# ESP_nixie_clock.net
KiCad netlist of a schematic drawn in EAGLE
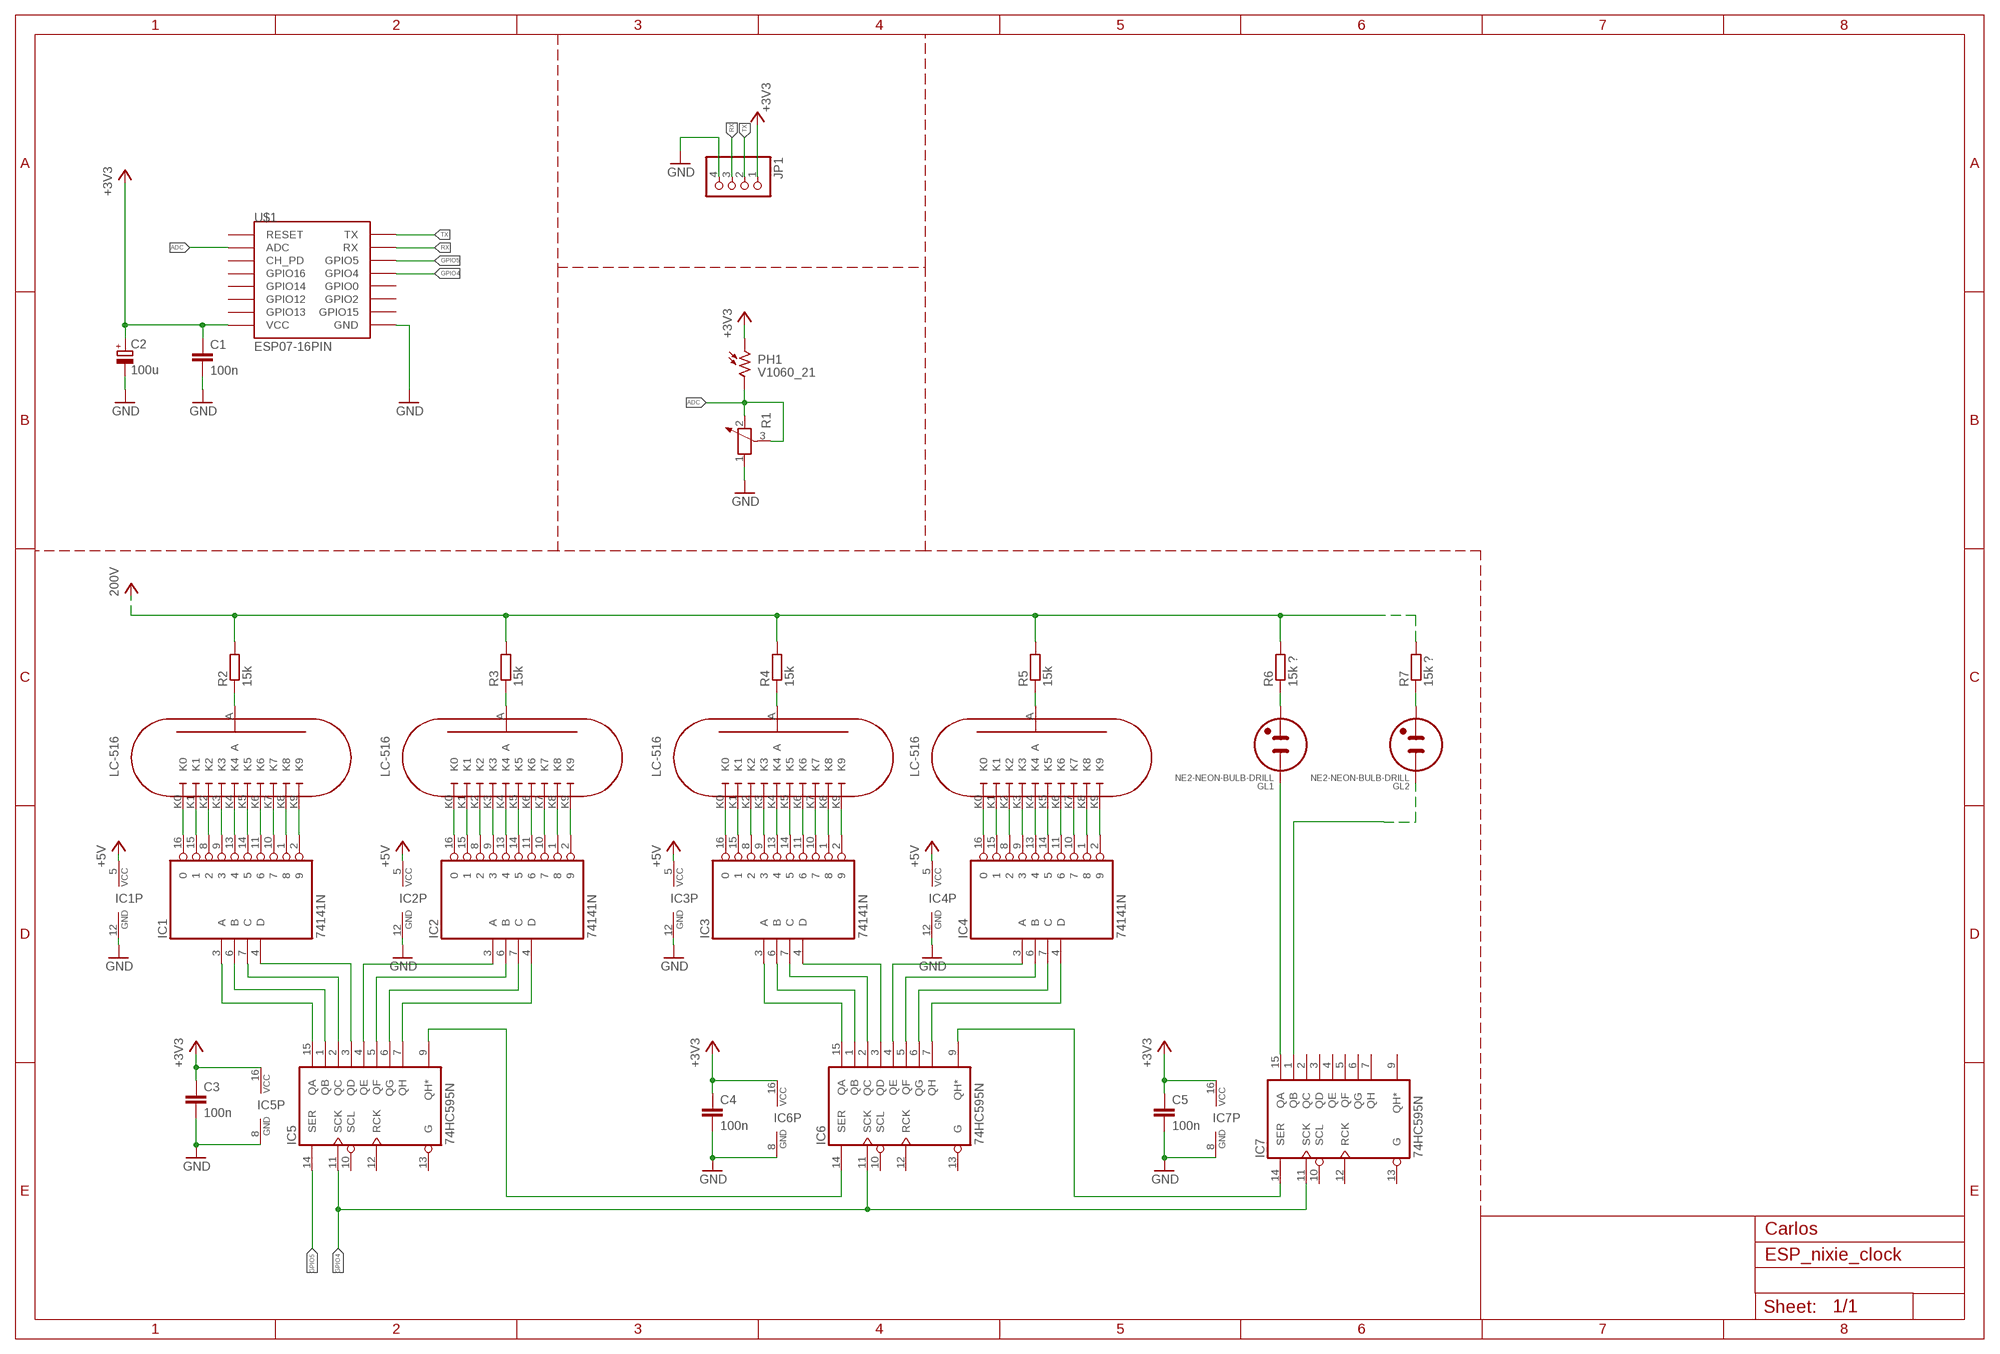
[diagram p0: schematic, sheet 1]

(export (version "E")
  (design (tool "Eeschema 10.0.6"))
  (components
    (comp (ref "C1")
      (value "100n")
      (footprint "eagle-import:C0805K")
      (libsource (lib "eagle-import") (part "C-EUC0805K"))
    )
    (comp (ref "C2")
      (value "100u")
      (footprint "eagle-import:153CLV-0810")
      (libsource (lib "eagle-import") (part "CPOL-EU153CLV-0810"))
    )
    (comp (ref "C3")
      (value "100n")
      (footprint "eagle-import:C0805K")
      (libsource (lib "eagle-import") (part "C-EUC0805K"))
    )
    (comp (ref "C4")
      (value "100n")
      (footprint "eagle-import:C0805K")
      (libsource (lib "eagle-import") (part "C-EUC0805K"))
    )
    (comp (ref "C5")
      (value "100n")
      (footprint "eagle-import:C0805K")
      (libsource (lib "eagle-import") (part "C-EUC0805K"))
    )
    (comp (ref "GL1")
      (value "NE2-NEON-BULB-DRILL")
      (footprint "eagle-import:NE2-NEON-BULB-DRILL")
      (libsource (lib "eagle-import") (part "NE2-NEON-BULB-DRILL"))
    )
    (comp (ref "GL2")
      (value "NE2-NEON-BULB-DRILL")
      (footprint "eagle-import:NE2-NEON-BULB-DRILL")
      (libsource (lib "eagle-import") (part "NE2-NEON-BULB-DRILL"))
    )
    (comp (ref "IC1")
      (value "74141N")
      (footprint "eagle-import:DIL16")
      (libsource (lib "eagle-import") (part "74141N"))
    )
    (comp (ref "IC2")
      (value "74141N")
      (footprint "eagle-import:DIL16")
      (libsource (lib "eagle-import") (part "74141N"))
    )
    (comp (ref "IC3")
      (value "74141N")
      (footprint "eagle-import:DIL16")
      (libsource (lib "eagle-import") (part "74141N"))
    )
    (comp (ref "IC4")
      (value "74141N")
      (footprint "eagle-import:DIL16")
      (libsource (lib "eagle-import") (part "74141N"))
    )
    (comp (ref "IC5")
      (value "74HC595N")
      (footprint "eagle-import:DIL16")
      (libsource (lib "eagle-import") (part "74595NHC"))
    )
    (comp (ref "IC6")
      (value "74HC595N")
      (footprint "eagle-import:DIL16")
      (libsource (lib "eagle-import") (part "74595NHC"))
    )
    (comp (ref "IC7")
      (value "74HC595N")
      (footprint "eagle-import:DIL16")
      (libsource (lib "eagle-import") (part "74595NHC"))
    )
    (comp (ref "JP1")
      (value "PINHD-1X4/90")
      (footprint "eagle-import:1X04_90")
      (libsource (lib "eagle-import") (part "PINHD-1X4/90"))
    )
    (comp (ref "PH1")
      (value "V1060_21")
      (footprint "eagle-import:TO-5_V10")
      (libsource (lib "eagle-import") (part "?1060V_21"))
    )
    (comp (ref "R1")
      (value "POTENTIOMETER_PT-10")
      (footprint "eagle-import:PT-10")
      (libsource (lib "eagle-import") (part "POTENTIOMETER_PT-10"))
    )
    (comp (ref "R2")
      (value "15k")
      (footprint "eagle-import:0207_10")
      (libsource (lib "eagle-import") (part "R-EU_0207/10"))
    )
    (comp (ref "R3")
      (value "15k")
      (footprint "eagle-import:0207_10")
      (libsource (lib "eagle-import") (part "R-EU_0207/10"))
    )
    (comp (ref "R4")
      (value "15k")
      (footprint "eagle-import:0207_10")
      (libsource (lib "eagle-import") (part "R-EU_0207/10"))
    )
    (comp (ref "R5")
      (value "15k")
      (footprint "eagle-import:0207_10")
      (libsource (lib "eagle-import") (part "R-EU_0207/10"))
    )
    (comp (ref "R6")
      (value "15k ?")
      (footprint "eagle-import:0207_10")
      (libsource (lib "eagle-import") (part "R-EU_0207/10"))
    )
    (comp (ref "R7")
      (value "15k ?")
      (footprint "eagle-import:0207_10")
      (libsource (lib "eagle-import") (part "R-EU_0207/10"))
    )
    (comp (ref "U$1")
      (value "ESP07-16PIN")
      (footprint "eagle-import:ESP07-16PIN")
      (libsource (lib "eagle-import") (part "ESP07-16PIN"))
    )
    (comp (ref "U$2")
      (value "LC-516")
      (footprint "eagle-import:LC-516")
      (libsource (lib "eagle-import") (part "LC-516"))
    )
    (comp (ref "U$3")
      (value "LC-516")
      (footprint "eagle-import:LC-516")
      (libsource (lib "eagle-import") (part "LC-516"))
    )
    (comp (ref "U$4")
      (value "LC-516")
      (footprint "eagle-import:LC-516")
      (libsource (lib "eagle-import") (part "LC-516"))
    )
    (comp (ref "U$5")
      (value "LC-516")
      (footprint "eagle-import:LC-516")
      (libsource (lib "eagle-import") (part "LC-516"))
    )
  )
  (nets
    (net (code "1") (name "+3V3") (class "Default")
      (node (ref "C1") (pin "1") (pinfunction "1_1") (pintype "passive"))
      (node (ref "C2") (pin "+") (pinfunction "+_+") (pintype "passive"))
      (node (ref "C3") (pin "1") (pinfunction "1_1") (pintype "passive"))
      (node (ref "C4") (pin "1") (pinfunction "1_1") (pintype "passive"))
      (node (ref "C5") (pin "1") (pinfunction "1_1") (pintype "passive"))
      (node (ref "IC5") (pin "16") (pinfunction "VCC_16") (pintype "power_in"))
      (node (ref "IC6") (pin "16") (pinfunction "VCC_16") (pintype "power_in"))
      (node (ref "IC7") (pin "16") (pinfunction "VCC_16") (pintype "power_in"))
      (node (ref "JP1") (pin "1") (pinfunction "1_1") (pintype "passive"))
      (node (ref "PH1") (pin "1") (pinfunction "1_1") (pintype "passive"))
      (node (ref "U$1") (pin "VCC") (pinfunction "VCC_VCC") (pintype "bidirectional"))
    )
    (net (code "2") (name "+5V") (class "Default")
      (node (ref "IC1") (pin "5") (pinfunction "VCC_5") (pintype "power_in"))
      (node (ref "IC2") (pin "5") (pinfunction "VCC_5") (pintype "power_in"))
      (node (ref "IC3") (pin "5") (pinfunction "VCC_5") (pintype "power_in"))
      (node (ref "IC4") (pin "5") (pinfunction "VCC_5") (pintype "power_in"))
    )
    (net (code "3") (name "200V") (class "Default")
      (node (ref "R2") (pin "2") (pinfunction "2_2") (pintype "passive"))
      (node (ref "R3") (pin "2") (pinfunction "2_2") (pintype "passive"))
      (node (ref "R4") (pin "2") (pinfunction "2_2") (pintype "passive"))
      (node (ref "R5") (pin "2") (pinfunction "2_2") (pintype "passive"))
      (node (ref "R6") (pin "2") (pinfunction "2_2") (pintype "passive"))
      (node (ref "R7") (pin "2") (pinfunction "2_2") (pintype "passive"))
    )
    (net (code "4") (name "ADC") (class "Default")
      (node (ref "PH1") (pin "2") (pinfunction "2_2") (pintype "passive"))
      (node (ref "R1") (pin "2") (pinfunction "2_2") (pintype "passive"))
      (node (ref "R1") (pin "3") (pinfunction "3_3") (pintype "passive"))
      (node (ref "U$1") (pin "ADC") (pinfunction "ADC_ADC") (pintype "bidirectional"))
    )
    (net (code "5") (name "GND") (class "Default")
      (node (ref "C1") (pin "2") (pinfunction "2_2") (pintype "passive"))
      (node (ref "C2") (pin "-") (pinfunction "-_-") (pintype "passive"))
      (node (ref "C3") (pin "2") (pinfunction "2_2") (pintype "passive"))
      (node (ref "C4") (pin "2") (pinfunction "2_2") (pintype "passive"))
      (node (ref "C5") (pin "2") (pinfunction "2_2") (pintype "passive"))
      (node (ref "IC1") (pin "12") (pinfunction "GND_12") (pintype "power_in"))
      (node (ref "IC2") (pin "12") (pinfunction "GND_12") (pintype "power_in"))
      (node (ref "IC3") (pin "12") (pinfunction "GND_12") (pintype "power_in"))
      (node (ref "IC4") (pin "12") (pinfunction "GND_12") (pintype "power_in"))
      (node (ref "IC5") (pin "8") (pinfunction "GND_8") (pintype "power_in"))
      (node (ref "IC6") (pin "8") (pinfunction "GND_8") (pintype "power_in"))
      (node (ref "IC7") (pin "8") (pinfunction "GND_8") (pintype "power_in"))
      (node (ref "JP1") (pin "4") (pinfunction "4_4") (pintype "passive"))
      (node (ref "R1") (pin "1") (pinfunction "1_1") (pintype "passive"))
      (node (ref "U$1") (pin "GND") (pinfunction "GND_GND") (pintype "bidirectional"))
    )
    (net (code "6") (name "GPIO4") (class "Default")
      (node (ref "IC5") (pin "11") (pinfunction "SCK_11") (pintype "input"))
      (node (ref "IC6") (pin "11") (pinfunction "SCK_11") (pintype "input"))
      (node (ref "IC7") (pin "11") (pinfunction "SCK_11") (pintype "input"))
      (node (ref "U$1") (pin "GPIO5") (pinfunction "GPIO4_GPIO5") (pintype "bidirectional"))
    )
    (net (code "7") (name "GPIO5") (class "Default")
      (node (ref "IC5") (pin "14") (pinfunction "SER_14") (pintype "input"))
      (node (ref "U$1") (pin "GPIO4") (pinfunction "GPIO5_GPIO4") (pintype "bidirectional"))
    )
    (net (code "8") (name "Net-(GL1-A)") (class "Default")
      (node (ref "GL1") (pin "1") (pinfunction "A_1") (pintype "passive"))
      (node (ref "IC7") (pin "15") (pinfunction "QA_15") (pintype "tri_state"))
    )
    (net (code "9") (name "Net-(GL1-A1)") (class "Default")
      (node (ref "GL1") (pin "2") (pinfunction "A1_2") (pintype "passive"))
      (node (ref "R6") (pin "1") (pinfunction "1_1") (pintype "passive"))
    )
    (net (code "10") (name "Net-(GL2-A)") (class "Default")
      (node (ref "GL2") (pin "1") (pinfunction "A_1") (pintype "passive"))
      (node (ref "IC7") (pin "1") (pinfunction "QB_1") (pintype "tri_state"))
    )
    (net (code "11") (name "Net-(GL2-A1)") (class "Default")
      (node (ref "GL2") (pin "2") (pinfunction "A1_2") (pintype "passive"))
      (node (ref "R7") (pin "1") (pinfunction "1_1") (pintype "passive"))
    )
    (net (code "12") (name "Net-(IC1A-0)") (class "Default")
      (node (ref "IC1") (pin "16") (pinfunction "0_16") (pintype "open_collector"))
      (node (ref "U$2") (pin "K0") (pinfunction "K0_K0") (pintype "bidirectional"))
    )
    (net (code "13") (name "Net-(IC1A-1)") (class "Default")
      (node (ref "IC1") (pin "15") (pinfunction "1_15") (pintype "open_collector"))
      (node (ref "U$2") (pin "K1") (pinfunction "K1_K1") (pintype "bidirectional"))
    )
    (net (code "14") (name "Net-(IC1A-2)") (class "Default")
      (node (ref "IC1") (pin "8") (pinfunction "2_8") (pintype "open_collector"))
      (node (ref "U$2") (pin "K2") (pinfunction "K2_K2") (pintype "bidirectional"))
    )
    (net (code "15") (name "Net-(IC1A-3)") (class "Default")
      (node (ref "IC1") (pin "9") (pinfunction "3_9") (pintype "open_collector"))
      (node (ref "U$2") (pin "K3") (pinfunction "K3_K3") (pintype "bidirectional"))
    )
    (net (code "16") (name "Net-(IC1A-4)") (class "Default")
      (node (ref "IC1") (pin "13") (pinfunction "4_13") (pintype "open_collector"))
      (node (ref "U$2") (pin "K4") (pinfunction "K4_K4") (pintype "bidirectional"))
    )
    (net (code "17") (name "Net-(IC1A-5)") (class "Default")
      (node (ref "IC1") (pin "14") (pinfunction "5_14") (pintype "open_collector"))
      (node (ref "U$2") (pin "K5") (pinfunction "K5_K5") (pintype "bidirectional"))
    )
    (net (code "18") (name "Net-(IC1A-6)") (class "Default")
      (node (ref "IC1") (pin "11") (pinfunction "6_11") (pintype "open_collector"))
      (node (ref "U$2") (pin "K6") (pinfunction "K6_K6") (pintype "bidirectional"))
    )
    (net (code "19") (name "Net-(IC1A-7)") (class "Default")
      (node (ref "IC1") (pin "10") (pinfunction "7_10") (pintype "open_collector"))
      (node (ref "U$2") (pin "K7") (pinfunction "K7_K7") (pintype "bidirectional"))
    )
    (net (code "20") (name "Net-(IC1A-8)") (class "Default")
      (node (ref "IC1") (pin "1") (pinfunction "8_1") (pintype "open_collector"))
      (node (ref "U$2") (pin "K8") (pinfunction "K8_K8") (pintype "bidirectional"))
    )
    (net (code "21") (name "Net-(IC1A-9)") (class "Default")
      (node (ref "IC1") (pin "2") (pinfunction "9_2") (pintype "open_collector"))
      (node (ref "U$2") (pin "K9") (pinfunction "K9_K9") (pintype "bidirectional"))
    )
    (net (code "22") (name "Net-(IC1A-A)") (class "Default")
      (node (ref "IC1") (pin "3") (pinfunction "A_3") (pintype "input"))
      (node (ref "IC5") (pin "15") (pinfunction "QA_15") (pintype "tri_state"))
    )
    (net (code "23") (name "Net-(IC1A-B)") (class "Default")
      (node (ref "IC1") (pin "6") (pinfunction "B_6") (pintype "input"))
      (node (ref "IC5") (pin "1") (pinfunction "QB_1") (pintype "tri_state"))
    )
    (net (code "24") (name "Net-(IC1A-C)") (class "Default")
      (node (ref "IC1") (pin "7") (pinfunction "C_7") (pintype "input"))
      (node (ref "IC5") (pin "2") (pinfunction "QC_2") (pintype "tri_state"))
    )
    (net (code "25") (name "Net-(IC1A-D)") (class "Default")
      (node (ref "IC1") (pin "4") (pinfunction "D_4") (pintype "input"))
      (node (ref "IC5") (pin "3") (pinfunction "QD_3") (pintype "tri_state"))
    )
    (net (code "26") (name "Net-(IC2A-0)") (class "Default")
      (node (ref "IC2") (pin "16") (pinfunction "0_16") (pintype "open_collector"))
      (node (ref "U$3") (pin "K0") (pinfunction "K0_K0") (pintype "bidirectional"))
    )
    (net (code "27") (name "Net-(IC2A-1)") (class "Default")
      (node (ref "IC2") (pin "15") (pinfunction "1_15") (pintype "open_collector"))
      (node (ref "U$3") (pin "K1") (pinfunction "K1_K1") (pintype "bidirectional"))
    )
    (net (code "28") (name "Net-(IC2A-2)") (class "Default")
      (node (ref "IC2") (pin "8") (pinfunction "2_8") (pintype "open_collector"))
      (node (ref "U$3") (pin "K2") (pinfunction "K2_K2") (pintype "bidirectional"))
    )
    (net (code "29") (name "Net-(IC2A-3)") (class "Default")
      (node (ref "IC2") (pin "9") (pinfunction "3_9") (pintype "open_collector"))
      (node (ref "U$3") (pin "K3") (pinfunction "K3_K3") (pintype "bidirectional"))
    )
    (net (code "30") (name "Net-(IC2A-4)") (class "Default")
      (node (ref "IC2") (pin "13") (pinfunction "4_13") (pintype "open_collector"))
      (node (ref "U$3") (pin "K4") (pinfunction "K4_K4") (pintype "bidirectional"))
    )
    (net (code "31") (name "Net-(IC2A-5)") (class "Default")
      (node (ref "IC2") (pin "14") (pinfunction "5_14") (pintype "open_collector"))
      (node (ref "U$3") (pin "K5") (pinfunction "K5_K5") (pintype "bidirectional"))
    )
    (net (code "32") (name "Net-(IC2A-6)") (class "Default")
      (node (ref "IC2") (pin "11") (pinfunction "6_11") (pintype "open_collector"))
      (node (ref "U$3") (pin "K6") (pinfunction "K6_K6") (pintype "bidirectional"))
    )
    (net (code "33") (name "Net-(IC2A-7)") (class "Default")
      (node (ref "IC2") (pin "10") (pinfunction "7_10") (pintype "open_collector"))
      (node (ref "U$3") (pin "K7") (pinfunction "K7_K7") (pintype "bidirectional"))
    )
    (net (code "34") (name "Net-(IC2A-8)") (class "Default")
      (node (ref "IC2") (pin "1") (pinfunction "8_1") (pintype "open_collector"))
      (node (ref "U$3") (pin "K8") (pinfunction "K8_K8") (pintype "bidirectional"))
    )
    (net (code "35") (name "Net-(IC2A-9)") (class "Default")
      (node (ref "IC2") (pin "2") (pinfunction "9_2") (pintype "open_collector"))
      (node (ref "U$3") (pin "K9") (pinfunction "K9_K9") (pintype "bidirectional"))
    )
    (net (code "36") (name "Net-(IC2A-A)") (class "Default")
      (node (ref "IC2") (pin "3") (pinfunction "A_3") (pintype "input"))
      (node (ref "IC5") (pin "4") (pinfunction "QE_4") (pintype "tri_state"))
    )
    (net (code "37") (name "Net-(IC2A-B)") (class "Default")
      (node (ref "IC2") (pin "6") (pinfunction "B_6") (pintype "input"))
      (node (ref "IC5") (pin "5") (pinfunction "QF_5") (pintype "tri_state"))
    )
    (net (code "38") (name "Net-(IC2A-C)") (class "Default")
      (node (ref "IC2") (pin "7") (pinfunction "C_7") (pintype "input"))
      (node (ref "IC5") (pin "6") (pinfunction "QG_6") (pintype "tri_state"))
    )
    (net (code "39") (name "Net-(IC2A-D)") (class "Default")
      (node (ref "IC2") (pin "4") (pinfunction "D_4") (pintype "input"))
      (node (ref "IC5") (pin "7") (pinfunction "QH_7") (pintype "tri_state"))
    )
    (net (code "40") (name "Net-(IC3A-0)") (class "Default")
      (node (ref "IC3") (pin "16") (pinfunction "0_16") (pintype "open_collector"))
      (node (ref "U$4") (pin "K0") (pinfunction "K0_K0") (pintype "bidirectional"))
    )
    (net (code "41") (name "Net-(IC3A-1)") (class "Default")
      (node (ref "IC3") (pin "15") (pinfunction "1_15") (pintype "open_collector"))
      (node (ref "U$4") (pin "K1") (pinfunction "K1_K1") (pintype "bidirectional"))
    )
    (net (code "42") (name "Net-(IC3A-2)") (class "Default")
      (node (ref "IC3") (pin "8") (pinfunction "2_8") (pintype "open_collector"))
      (node (ref "U$4") (pin "K2") (pinfunction "K2_K2") (pintype "bidirectional"))
    )
    (net (code "43") (name "Net-(IC3A-3)") (class "Default")
      (node (ref "IC3") (pin "9") (pinfunction "3_9") (pintype "open_collector"))
      (node (ref "U$4") (pin "K3") (pinfunction "K3_K3") (pintype "bidirectional"))
    )
    (net (code "44") (name "Net-(IC3A-4)") (class "Default")
      (node (ref "IC3") (pin "13") (pinfunction "4_13") (pintype "open_collector"))
      (node (ref "U$4") (pin "K4") (pinfunction "K4_K4") (pintype "bidirectional"))
    )
    (net (code "45") (name "Net-(IC3A-5)") (class "Default")
      (node (ref "IC3") (pin "14") (pinfunction "5_14") (pintype "open_collector"))
      (node (ref "U$4") (pin "K5") (pinfunction "K5_K5") (pintype "bidirectional"))
    )
    (net (code "46") (name "Net-(IC3A-6)") (class "Default")
      (node (ref "IC3") (pin "11") (pinfunction "6_11") (pintype "open_collector"))
      (node (ref "U$4") (pin "K6") (pinfunction "K6_K6") (pintype "bidirectional"))
    )
    (net (code "47") (name "Net-(IC3A-7)") (class "Default")
      (node (ref "IC3") (pin "10") (pinfunction "7_10") (pintype "open_collector"))
      (node (ref "U$4") (pin "K7") (pinfunction "K7_K7") (pintype "bidirectional"))
    )
    (net (code "48") (name "Net-(IC3A-8)") (class "Default")
      (node (ref "IC3") (pin "1") (pinfunction "8_1") (pintype "open_collector"))
      (node (ref "U$4") (pin "K8") (pinfunction "K8_K8") (pintype "bidirectional"))
    )
    (net (code "49") (name "Net-(IC3A-9)") (class "Default")
      (node (ref "IC3") (pin "2") (pinfunction "9_2") (pintype "open_collector"))
      (node (ref "U$4") (pin "K9") (pinfunction "K9_K9") (pintype "bidirectional"))
    )
    (net (code "50") (name "Net-(IC3A-A)") (class "Default")
      (node (ref "IC3") (pin "3") (pinfunction "A_3") (pintype "input"))
      (node (ref "IC6") (pin "15") (pinfunction "QA_15") (pintype "tri_state"))
    )
    (net (code "51") (name "Net-(IC3A-B)") (class "Default")
      (node (ref "IC3") (pin "6") (pinfunction "B_6") (pintype "input"))
      (node (ref "IC6") (pin "1") (pinfunction "QB_1") (pintype "tri_state"))
    )
    (net (code "52") (name "Net-(IC3A-C)") (class "Default")
      (node (ref "IC3") (pin "7") (pinfunction "C_7") (pintype "input"))
      (node (ref "IC6") (pin "2") (pinfunction "QC_2") (pintype "tri_state"))
    )
    (net (code "53") (name "Net-(IC3A-D)") (class "Default")
      (node (ref "IC3") (pin "4") (pinfunction "D_4") (pintype "input"))
      (node (ref "IC6") (pin "3") (pinfunction "QD_3") (pintype "tri_state"))
    )
    (net (code "54") (name "Net-(IC4A-0)") (class "Default")
      (node (ref "IC4") (pin "16") (pinfunction "0_16") (pintype "open_collector"))
      (node (ref "U$5") (pin "K0") (pinfunction "K0_K0") (pintype "bidirectional"))
    )
    (net (code "55") (name "Net-(IC4A-1)") (class "Default")
      (node (ref "IC4") (pin "15") (pinfunction "1_15") (pintype "open_collector"))
      (node (ref "U$5") (pin "K1") (pinfunction "K1_K1") (pintype "bidirectional"))
    )
    (net (code "56") (name "Net-(IC4A-2)") (class "Default")
      (node (ref "IC4") (pin "8") (pinfunction "2_8") (pintype "open_collector"))
      (node (ref "U$5") (pin "K2") (pinfunction "K2_K2") (pintype "bidirectional"))
    )
    (net (code "57") (name "Net-(IC4A-3)") (class "Default")
      (node (ref "IC4") (pin "9") (pinfunction "3_9") (pintype "open_collector"))
      (node (ref "U$5") (pin "K3") (pinfunction "K3_K3") (pintype "bidirectional"))
    )
    (net (code "58") (name "Net-(IC4A-4)") (class "Default")
      (node (ref "IC4") (pin "13") (pinfunction "4_13") (pintype "open_collector"))
      (node (ref "U$5") (pin "K4") (pinfunction "K4_K4") (pintype "bidirectional"))
    )
    (net (code "59") (name "Net-(IC4A-5)") (class "Default")
      (node (ref "IC4") (pin "14") (pinfunction "5_14") (pintype "open_collector"))
      (node (ref "U$5") (pin "K5") (pinfunction "K5_K5") (pintype "bidirectional"))
    )
    (net (code "60") (name "Net-(IC4A-6)") (class "Default")
      (node (ref "IC4") (pin "11") (pinfunction "6_11") (pintype "open_collector"))
      (node (ref "U$5") (pin "K6") (pinfunction "K6_K6") (pintype "bidirectional"))
    )
    (net (code "61") (name "Net-(IC4A-7)") (class "Default")
      (node (ref "IC4") (pin "10") (pinfunction "7_10") (pintype "open_collector"))
      (node (ref "U$5") (pin "K7") (pinfunction "K7_K7") (pintype "bidirectional"))
    )
    (net (code "62") (name "Net-(IC4A-8)") (class "Default")
      (node (ref "IC4") (pin "1") (pinfunction "8_1") (pintype "open_collector"))
      (node (ref "U$5") (pin "K8") (pinfunction "K8_K8") (pintype "bidirectional"))
    )
    (net (code "63") (name "Net-(IC4A-9)") (class "Default")
      (node (ref "IC4") (pin "2") (pinfunction "9_2") (pintype "open_collector"))
      (node (ref "U$5") (pin "K9") (pinfunction "K9_K9") (pintype "bidirectional"))
    )
    (net (code "64") (name "Net-(IC4A-A)") (class "Default")
      (node (ref "IC4") (pin "3") (pinfunction "A_3") (pintype "input"))
      (node (ref "IC6") (pin "4") (pinfunction "QE_4") (pintype "tri_state"))
    )
    (net (code "65") (name "Net-(IC4A-B)") (class "Default")
      (node (ref "IC4") (pin "6") (pinfunction "B_6") (pintype "input"))
      (node (ref "IC6") (pin "5") (pinfunction "QF_5") (pintype "tri_state"))
    )
    (net (code "66") (name "Net-(IC4A-C)") (class "Default")
      (node (ref "IC4") (pin "7") (pinfunction "C_7") (pintype "input"))
      (node (ref "IC6") (pin "6") (pinfunction "QG_6") (pintype "tri_state"))
    )
    (net (code "67") (name "Net-(IC4A-D)") (class "Default")
      (node (ref "IC4") (pin "4") (pinfunction "D_4") (pintype "input"))
      (node (ref "IC6") (pin "7") (pinfunction "QH_7") (pintype "tri_state"))
    )
    (net (code "68") (name "Net-(IC5A-QH*)") (class "Default")
      (node (ref "IC5") (pin "9") (pinfunction "QH*_9") (pintype "tri_state"))
      (node (ref "IC6") (pin "14") (pinfunction "SER_14") (pintype "input"))
    )
    (net (code "69") (name "Net-(IC6A-QH*)") (class "Default")
      (node (ref "IC6") (pin "9") (pinfunction "QH*_9") (pintype "tri_state"))
      (node (ref "IC7") (pin "14") (pinfunction "SER_14") (pintype "input"))
    )
    (net (code "70") (name "Net-(R2-Pad1)") (class "Default")
      (node (ref "R2") (pin "1") (pinfunction "1_1") (pintype "passive"))
      (node (ref "U$2") (pin "A") (pinfunction "A_A") (pintype "bidirectional"))
    )
    (net (code "71") (name "Net-(R3-Pad1)") (class "Default")
      (node (ref "R3") (pin "1") (pinfunction "1_1") (pintype "passive"))
      (node (ref "U$3") (pin "A") (pinfunction "A_A") (pintype "bidirectional"))
    )
    (net (code "72") (name "Net-(R4-Pad1)") (class "Default")
      (node (ref "R4") (pin "1") (pinfunction "1_1") (pintype "passive"))
      (node (ref "U$4") (pin "A") (pinfunction "A_A") (pintype "bidirectional"))
    )
    (net (code "73") (name "Net-(R5-Pad1)") (class "Default")
      (node (ref "R5") (pin "1") (pinfunction "1_1") (pintype "passive"))
      (node (ref "U$5") (pin "A") (pinfunction "A_A") (pintype "bidirectional"))
    )
    (net (code "74") (name "RX") (class "Default")
      (node (ref "JP1") (pin "3") (pinfunction "3_3") (pintype "passive"))
      (node (ref "U$1") (pin "RX") (pinfunction "RX_RX") (pintype "bidirectional"))
    )
    (net (code "75") (name "TX") (class "Default")
      (node (ref "JP1") (pin "2") (pinfunction "2_2") (pintype "passive"))
      (node (ref "U$1") (pin "TX") (pinfunction "TX_TX") (pintype "bidirectional"))
    )
    (net (code "76") (name "unconnected-(IC5A-G-Pad13)") (class "Default")
      (node (ref "IC5") (pin "13") (pinfunction "G_13") (pintype "input"))
    )
    (net (code "77") (name "unconnected-(IC5A-RCK-Pad12)") (class "Default")
      (node (ref "IC5") (pin "12") (pinfunction "RCK_12") (pintype "input"))
    )
    (net (code "78") (name "unconnected-(IC5A-SCL-Pad10)") (class "Default")
      (node (ref "IC5") (pin "10") (pinfunction "SCL_10") (pintype "input"))
    )
    (net (code "79") (name "unconnected-(IC6A-G-Pad13)") (class "Default")
      (node (ref "IC6") (pin "13") (pinfunction "G_13") (pintype "input"))
    )
    (net (code "80") (name "unconnected-(IC6A-RCK-Pad12)") (class "Default")
      (node (ref "IC6") (pin "12") (pinfunction "RCK_12") (pintype "input"))
    )
    (net (code "81") (name "unconnected-(IC6A-SCL-Pad10)") (class "Default")
      (node (ref "IC6") (pin "10") (pinfunction "SCL_10") (pintype "input"))
    )
    (net (code "82") (name "unconnected-(IC7A-G-Pad13)") (class "Default")
      (node (ref "IC7") (pin "13") (pinfunction "G_13") (pintype "input"))
    )
    (net (code "83") (name "unconnected-(IC7A-QC-Pad2)") (class "Default")
      (node (ref "IC7") (pin "2") (pinfunction "QC_2") (pintype "tri_state"))
    )
    (net (code "84") (name "unconnected-(IC7A-QD-Pad3)") (class "Default")
      (node (ref "IC7") (pin "3") (pinfunction "QD_3") (pintype "tri_state"))
    )
    (net (code "85") (name "unconnected-(IC7A-QE-Pad4)") (class "Default")
      (node (ref "IC7") (pin "4") (pinfunction "QE_4") (pintype "tri_state"))
    )
    (net (code "86") (name "unconnected-(IC7A-QF-Pad5)") (class "Default")
      (node (ref "IC7") (pin "5") (pinfunction "QF_5") (pintype "tri_state"))
    )
    (net (code "87") (name "unconnected-(IC7A-QG-Pad6)") (class "Default")
      (node (ref "IC7") (pin "6") (pinfunction "QG_6") (pintype "tri_state"))
    )
    (net (code "88") (name "unconnected-(IC7A-QH*-Pad9)") (class "Default")
      (node (ref "IC7") (pin "9") (pinfunction "QH*_9") (pintype "tri_state"))
    )
    (net (code "89") (name "unconnected-(IC7A-QH-Pad7)") (class "Default")
      (node (ref "IC7") (pin "7") (pinfunction "QH_7") (pintype "tri_state"))
    )
    (net (code "90") (name "unconnected-(IC7A-RCK-Pad12)") (class "Default")
      (node (ref "IC7") (pin "12") (pinfunction "RCK_12") (pintype "input"))
    )
    (net (code "91") (name "unconnected-(IC7A-SCL-Pad10)") (class "Default")
      (node (ref "IC7") (pin "10") (pinfunction "SCL_10") (pintype "input"))
    )
    (net (code "92") (name "unconnected-(U$1-PadCH_PD)") (class "Default")
      (node (ref "U$1") (pin "CH_PD") (pinfunction "CH_PD_CH_PD") (pintype "bidirectional"))
    )
    (net (code "93") (name "unconnected-(U$1-PadGPIO0)") (class "Default")
      (node (ref "U$1") (pin "GPIO0") (pinfunction "GPIO0_GPIO0") (pintype "bidirectional"))
    )
    (net (code "94") (name "unconnected-(U$1-PadGPIO2)") (class "Default")
      (node (ref "U$1") (pin "GPIO2") (pinfunction "GPIO2_GPIO2") (pintype "bidirectional"))
    )
    (net (code "95") (name "unconnected-(U$1-PadGPIO12)") (class "Default")
      (node (ref "U$1") (pin "GPIO12") (pinfunction "GPIO12_GPIO12") (pintype "bidirectional"))
    )
    (net (code "96") (name "unconnected-(U$1-PadGPIO13)") (class "Default")
      (node (ref "U$1") (pin "GPIO13") (pinfunction "GPIO13_GPIO13") (pintype "bidirectional"))
    )
    (net (code "97") (name "unconnected-(U$1-PadGPIO14)") (class "Default")
      (node (ref "U$1") (pin "GPIO14") (pinfunction "GPIO14_GPIO14") (pintype "bidirectional"))
    )
    (net (code "98") (name "unconnected-(U$1-PadGPIO15)") (class "Default")
      (node (ref "U$1") (pin "GPIO15") (pinfunction "GPIO15_GPIO15") (pintype "bidirectional"))
    )
    (net (code "99") (name "unconnected-(U$1-PadGPIO16)") (class "Default")
      (node (ref "U$1") (pin "GPIO16") (pinfunction "GPIO16_GPIO16") (pintype "bidirectional"))
    )
    (net (code "100") (name "unconnected-(U$1-RESET-PadREST)") (class "Default")
      (node (ref "U$1") (pin "REST") (pinfunction "RESET_REST") (pintype "bidirectional"))
    )
  )
)
